# Ethernet.net
KiCad netlist of a schematic drawn in Altium Designer
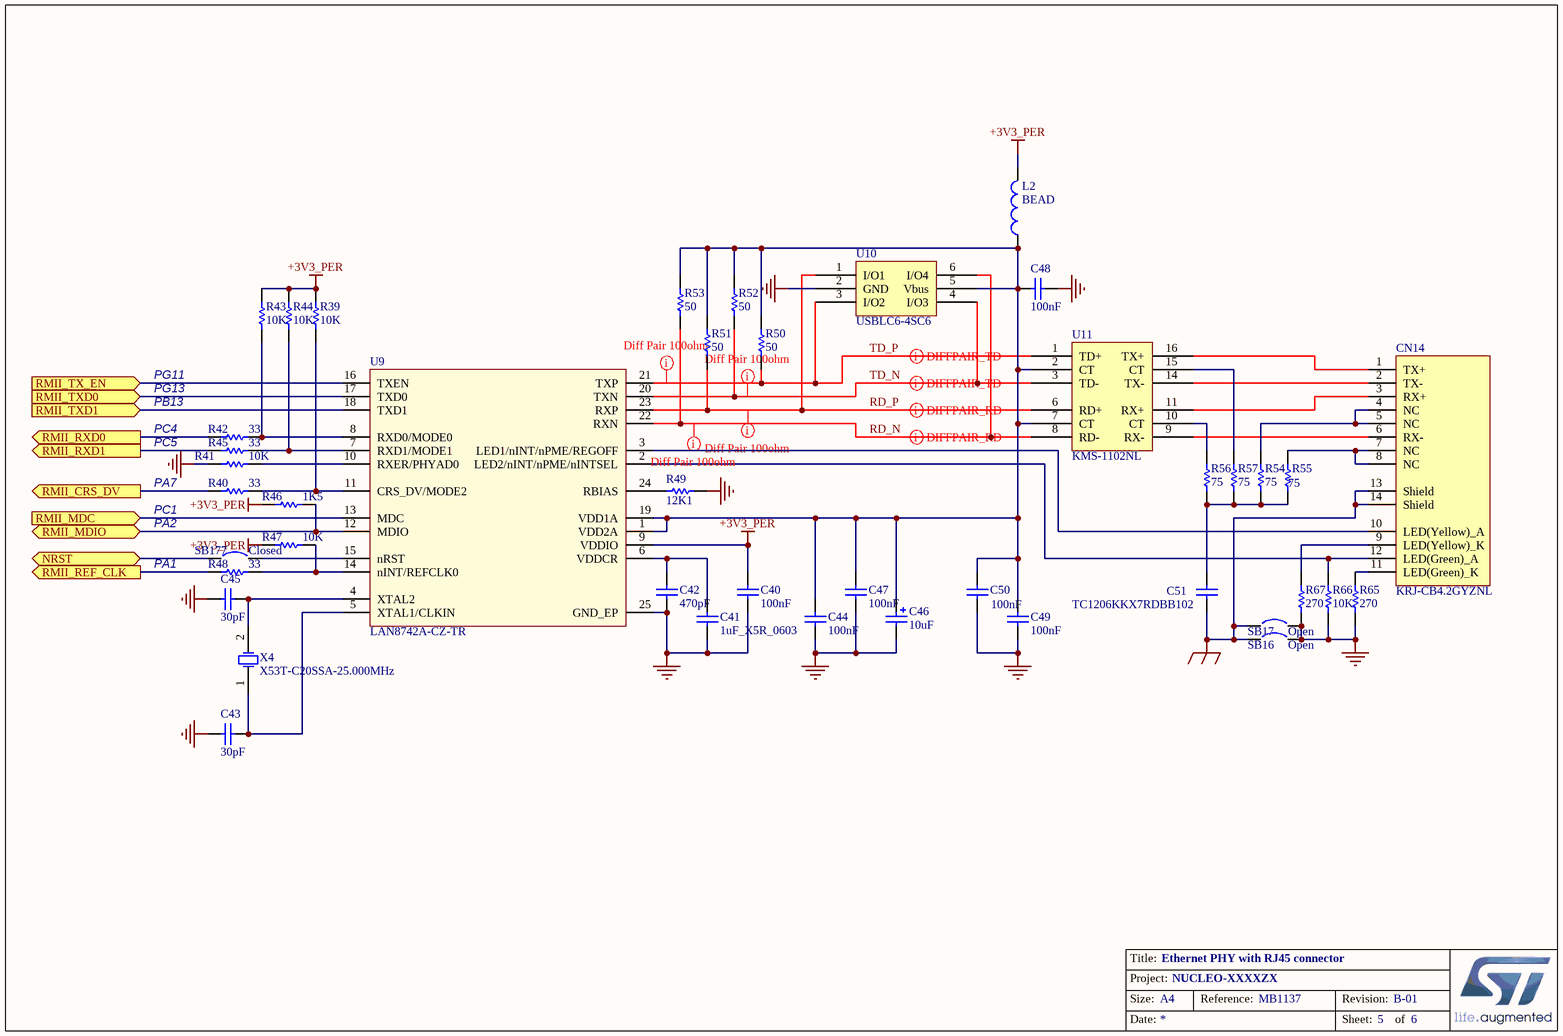
[diagram p0: Ethernet.SchDoc]

(export (version "E")
  (design (tool "Eeschema 10.0.6"))
  (components
    (comp (ref "C40")
      (value "100nF")
      (footprint "0603C")
      (description "Capacitor 0402 / 0603 / 0805")
      (libsource (lib "MCD_TOOLS") (part "Capacitor_ST"))
    )
    (comp (ref "C41")
      (value "1uF_X5R_0603")
      (footprint "0603C")
      (description "0603  X5R 1µF")
      (fields (field (name "TOLERANCE") "10%"))
      (libsource (lib "MB963_1") (part "CAP SMD 0603  X5R 1µF 25V 10%"))
    )
    (comp (ref "C42")
      (value "470pF")
      (footprint "0603C")
      (description "Capacitor 0402 / 0603 / 0805")
      (libsource (lib "MCD_TOOLS") (part "Capacitor_ST"))
    )
    (comp (ref "C43")
      (value "30pF")
      (footprint "0603C")
      (description "Capacitor 0402 / 0603 / 0805")
      (libsource (lib "MCD_TOOLS") (part "Capacitor_ST"))
    )
    (comp (ref "C44")
      (value "100nF")
      (footprint "0603C")
      (description "Capacitor 0402 / 0603 / 0805")
      (libsource (lib "MCD_TOOLS") (part "Capacitor_ST"))
    )
    (comp (ref "C45")
      (value "30pF")
      (footprint "0603C")
      (description "Capacitor 0402 / 0603 / 0805")
      (libsource (lib "MCD_TOOLS") (part "Capacitor_ST"))
    )
    (comp (ref "C46")
      (value "10uF")
      (footprint "TAN-A")
      (description "Polarized Capacitor,10uF,10V,10%,typeA,VISHAY")
      (libsource (lib "MCD_TOOLS") (part "Cap_10uF_POL_10%_TANA"))
    )
    (comp (ref "C47")
      (value "100nF")
      (footprint "0603C")
      (description "Capacitor 0402 / 0603 / 0805")
      (libsource (lib "MCD_TOOLS") (part "Capacitor_ST"))
    )
    (comp (ref "C48")
      (value "100nF")
      (footprint "0603C")
      (description "Capacitor 0402 / 0603 / 0805")
      (libsource (lib "MCD_TOOLS") (part "Capacitor_ST"))
    )
    (comp (ref "C49")
      (value "100nF")
      (footprint "0603C")
      (description "Capacitor 0402 / 0603 / 0805")
      (libsource (lib "MCD_TOOLS") (part "Capacitor_ST"))
    )
    (comp (ref "C50")
      (value "100nF")
      (footprint "0603C")
      (description "Capacitor 0402 / 0603 / 0805")
      (libsource (lib "MCD_TOOLS") (part "Capacitor_ST"))
    )
    (comp (ref "C51")
      (value "TC1206KKX7RDBB102")
      (footprint "1206C")
      (description "Capacitor 0402 / 0603 / 0805/ 1206")
      (libsource (lib "MCD_TOOLS") (part "Capacitor_ST"))
    )
    (comp (ref "CN14")
      (value "KRJ-CB4.2GYZNL")
      (footprint "RJ45_KRJ-CB4.2GYZNL")
      (description "100 Base-TX (Fast Ethernet) SMD RJ45 single port (1x1) with LEDS Integrated Magnetics Connector")
      (libsource (lib "MB1137") (part "KRJ-CB4.2GYZNL"))
    )
    (comp (ref "L2")
      (value "BEAD")
      (footprint "0603L")
      (description "Inductor")
      (fields (field (name "PUBLISHER") "Altium Limited"))
      (libsource (lib "Miscellaneous Devices") (part "Inductor"))
    )
    (comp (ref "R39")
      (value "10K")
      (footprint "0603R")
      (description "Resistor 0402 or 0603 or 0805")
      (libsource (lib "Miscellaneous Devices") (part "Res1"))
    )
    (comp (ref "R40")
      (value "33")
      (footprint "0603R")
      (description "Resistor,33,0402,1%,YAGEO")
      (libsource (lib "MCD_TOOLS") (part "Res_33_1%_0402"))
    )
    (comp (ref "R41")
      (value "10K")
      (footprint "0603R")
      (description "Resistor 0402 or 0603 or 0805")
      (libsource (lib "Miscellaneous Devices") (part "Res1"))
    )
    (comp (ref "R42")
      (value "33")
      (footprint "0603R")
      (description "Resistor,33,0402,1%,YAGEO")
      (libsource (lib "MCD_TOOLS") (part "Res_33_1%_0402"))
    )
    (comp (ref "R43")
      (value "10K")
      (footprint "0603R")
      (description "Resistor 0402 or 0603 or 0805")
      (libsource (lib "Miscellaneous Devices") (part "Res1"))
    )
    (comp (ref "R44")
      (value "10K")
      (footprint "0603R")
      (description "Resistor 0402 or 0603 or 0805")
      (libsource (lib "Miscellaneous Devices") (part "Res1"))
    )
    (comp (ref "R45")
      (value "33")
      (footprint "0603R")
      (description "Resistor,33,0402,1%,YAGEO")
      (libsource (lib "MCD_TOOLS") (part "Res_33_1%_0402"))
    )
    (comp (ref "R46")
      (value "1K5")
      (footprint "0603R")
      (description "Resistor,1K5,0402,1%,YAGEO")
      (libsource (lib "MCD_TOOLS") (part "Res_1K5_1%_0402"))
    )
    (comp (ref "R47")
      (value "10K")
      (footprint "0603R")
      (description "Resistor 0402 or 0603 or 0805")
      (libsource (lib "Miscellaneous Devices") (part "Res1"))
    )
    (comp (ref "R48")
      (value "33")
      (footprint "0603R")
      (description "Resistor,33,0402,1%,YAGEO")
      (libsource (lib "MCD_TOOLS") (part "Res_33_1%_0402"))
    )
    (comp (ref "R49")
      (value "12K1")
      (footprint "0603R")
      (description "Resistor,12K1,0603,1%,VISHAY")
      (libsource (lib "MCD_TOOLS") (part "Res_12K1_1%_0603"))
    )
    (comp (ref "R50")
      (value "50")
      (footprint "0603R")
      (description "Resistor,50,0402,1%,YAGEO")
      (libsource (lib "MB1137") (part "Res_50_1%_0603"))
    )
    (comp (ref "R51")
      (value "50")
      (footprint "0603R")
      (description "Resistor,50,0402,1%,YAGEO")
      (libsource (lib "MB1137") (part "Res_50_1%_0603"))
    )
    (comp (ref "R52")
      (value "50")
      (footprint "0603R")
      (description "Resistor,50,0402,1%,YAGEO")
      (libsource (lib "MB1137") (part "Res_50_1%_0603"))
    )
    (comp (ref "R53")
      (value "50")
      (footprint "0603R")
      (description "Resistor,50,0402,1%,YAGEO")
      (libsource (lib "MB1137") (part "Res_50_1%_0603"))
    )
    (comp (ref "R54")
      (value "75")
      (footprint "0603R")
      (description "Resistor,50,0402,1%,YAGEO")
      (libsource (lib "MB1137") (part "Res_75_1%_0603"))
    )
    (comp (ref "R55")
      (value "75")
      (footprint "0603R")
      (description "Resistor,50,0402,1%,YAGEO")
      (libsource (lib "MB1137") (part "Res_75_1%_0603"))
    )
    (comp (ref "R56")
      (value "75")
      (footprint "0603R")
      (description "Resistor,50,0402,1%,YAGEO")
      (libsource (lib "MB1137") (part "Res_75_1%_0603"))
    )
    (comp (ref "R57")
      (value "75")
      (footprint "0603R")
      (description "Resistor,50,0402,1%,YAGEO")
      (libsource (lib "MB1137") (part "Res_75_1%_0603"))
    )
    (comp (ref "R65")
      (value "270")
      (footprint "0603R")
      (description "Resistor 0402 or 0603 or 0805")
      (libsource (lib "Miscellaneous Devices") (part "Res1"))
    )
    (comp (ref "R66")
      (value "10K")
      (footprint "0603R")
      (description "Resistor 0402 or 0603 or 0805")
      (libsource (lib "Miscellaneous Devices") (part "Res1"))
    )
    (comp (ref "R67")
      (value "270")
      (footprint "0603R")
      (description "Resistor 0402 or 0603 or 0805")
      (libsource (lib "Miscellaneous Devices") (part "Res1"))
    )
    (comp (ref "SB16")
      (value "Open")
      (footprint "SB_0603")
      (description "Circuit Breaker")
      (fields (field (name "PUBLISHER") "Altium Limited"))
      (libsource (lib "MB1167") (part "Circuit Breaker"))
    )
    (comp (ref "SB17")
      (value "Open")
      (footprint "SB_0603")
      (description "Circuit Breaker")
      (fields (field (name "PUBLISHER") "Altium Limited"))
      (libsource (lib "MB1167") (part "Circuit Breaker"))
    )
    (comp (ref "SB177")
      (value "Closed")
      (footprint "SB_0603")
      (description "Circuit Breaker")
      (fields (field (name "PUBLISHER") "Altium Limited"))
      (libsource (lib "MB1167") (part "Circuit Breaker_close"))
    )
    (comp (ref "U9")
      (value "LAN8742A-CZ-TR")
      (footprint "QFN24_0R5_4X4")
      (libsource (lib "MB1137") (part "LAN8742A-CZ-TR"))
    )
    (comp (ref "U10")
      (value "USBLC6-4SC6")
      (footprint "SOT23-6L")
      (libsource (lib "MB1137_1") (part "USBLC6-4SC6"))
    )
    (comp (ref "U11")
      (value "KMS-1102NL")
      (footprint "Transformer")
      (libsource (lib "MB1137") (part "KMS-1102NL"))
    )
    (comp (ref "X4")
      (value "X53T-C20SSA-25.000MHz")
      (footprint "XTAL_2SM_5R0X3R2")
      (description "Crystal Oscillator")
      (fields (field (name "PUBLISHER") "Altium Limited"))
      (libsource (lib "MB1137") (part "XTAL_5032"))
    )
  )
  (nets
    (net (code "1") (name "+3V3_PER") (class "Default")
      (node (ref "C40") (pin "2") (pinfunction "2_2") (pintype "passive"))
      (node (ref "L2") (pin "2") (pinfunction "2_2") (pintype "passive"))
      (node (ref "R39") (pin "1") (pinfunction "1_1") (pintype "passive"))
      (node (ref "R43") (pin "1") (pinfunction "1_1") (pintype "passive"))
      (node (ref "R44") (pin "1") (pinfunction "1_1") (pintype "passive"))
      (node (ref "R46") (pin "2") (pinfunction "2_2") (pintype "passive"))
      (node (ref "R47") (pin "1") (pinfunction "1_1") (pintype "passive"))
      (node (ref "U9") (pin "9") (pinfunction "VDDIO_9") (pintype "passive"))
    )
    (net (code "2") (name "/NRST") (class "Default")
      (node (ref "SB177") (pin "1") (pinfunction "1_1") (pintype "passive"))
    )
    (net (code "3") (name "/RD_N") (class "Default")
      (node (ref "R53") (pin "1") (pinfunction "1_1") (pintype "passive"))
      (node (ref "U10") (pin "6") (pinfunction "I/O4_6") (pintype "passive"))
      (node (ref "U11") (pin "8") (pinfunction "RD-_8") (pintype "passive"))
      (node (ref "U9") (pin "22") (pinfunction "RXN_22") (pintype "passive"))
    )
    (net (code "4") (name "/RD_P") (class "Default")
      (node (ref "R51") (pin "1") (pinfunction "1_1") (pintype "passive"))
      (node (ref "U10") (pin "1") (pinfunction "I/O1_1") (pintype "passive"))
      (node (ref "U11") (pin "6") (pinfunction "RD+_6") (pintype "passive"))
      (node (ref "U9") (pin "23") (pinfunction "RXP_23") (pintype "passive"))
    )
    (net (code "5") (name "/RMII_CRS_DV") (class "Default")
      (node (ref "R40") (pin "2") (pinfunction "2_2") (pintype "passive"))
    )
    (net (code "6") (name "/RMII_MDC") (class "Default")
      (node (ref "U9") (pin "13") (pinfunction "MDC_13") (pintype "passive"))
    )
    (net (code "7") (name "/RMII_MDIO") (class "Default")
      (node (ref "R46") (pin "1") (pinfunction "1_1") (pintype "passive"))
      (node (ref "U9") (pin "12") (pinfunction "MDIO_12") (pintype "passive"))
    )
    (net (code "8") (name "/RMII_REF_CLK") (class "Default")
      (node (ref "R48") (pin "2") (pinfunction "2_2") (pintype "passive"))
    )
    (net (code "9") (name "/RMII_RXD0") (class "Default")
      (node (ref "R42") (pin "2") (pinfunction "2_2") (pintype "passive"))
    )
    (net (code "10") (name "/RMII_RXD1") (class "Default")
      (node (ref "R45") (pin "2") (pinfunction "2_2") (pintype "passive"))
    )
    (net (code "11") (name "/RMII_TXD0") (class "Default")
      (node (ref "U9") (pin "17") (pinfunction "TXD0_17") (pintype "passive"))
    )
    (net (code "12") (name "/RMII_TXD1") (class "Default")
      (node (ref "U9") (pin "18") (pinfunction "TXD1_18") (pintype "passive"))
    )
    (net (code "13") (name "/RMII_TX_EN") (class "Default")
      (node (ref "U9") (pin "16") (pinfunction "TXEN_16") (pintype "passive"))
    )
    (net (code "14") (name "/TD_N") (class "Default")
      (node (ref "R52") (pin "1") (pinfunction "1_1") (pintype "passive"))
      (node (ref "U10") (pin "4") (pinfunction "I/O3_4") (pintype "passive"))
      (node (ref "U11") (pin "3") (pinfunction "TD-_3") (pintype "passive"))
      (node (ref "U9") (pin "20") (pinfunction "TXN_20") (pintype "passive"))
    )
    (net (code "15") (name "/TD_P") (class "Default")
      (node (ref "R50") (pin "1") (pinfunction "1_1") (pintype "passive"))
      (node (ref "U10") (pin "3") (pinfunction "I/O2_3") (pintype "passive"))
      (node (ref "U11") (pin "1") (pinfunction "TD+_1") (pintype "passive"))
      (node (ref "U9") (pin "21") (pinfunction "TXP_21") (pintype "passive"))
    )
    (net (code "16") (name "EGND") (class "Default")
      (node (ref "C51") (pin "1") (pinfunction "1_1") (pintype "passive"))
      (node (ref "CN14") (pin "13") (pinfunction "Shield_13") (pintype "passive"))
      (node (ref "CN14") (pin "14") (pinfunction "Shield_14") (pintype "passive"))
      (node (ref "SB16") (pin "1") (pinfunction "1_1") (pintype "passive"))
      (node (ref "SB17") (pin "1") (pinfunction "1_1") (pintype "passive"))
    )
    (net (code "17") (name "GND") (class "Default")
      (node (ref "C40") (pin "1") (pinfunction "1_1") (pintype "passive"))
      (node (ref "C41") (pin "2") (pinfunction "2_2") (pintype "passive"))
      (node (ref "C42") (pin "1") (pinfunction "1_1") (pintype "passive"))
      (node (ref "C43") (pin "2") (pinfunction "2_2") (pintype "passive"))
      (node (ref "C44") (pin "1") (pinfunction "1_1") (pintype "passive"))
      (node (ref "C45") (pin "2") (pinfunction "2_2") (pintype "passive"))
      (node (ref "C46") (pin "2") (pinfunction "2_2") (pintype "passive"))
      (node (ref "C47") (pin "1") (pinfunction "1_1") (pintype "passive"))
      (node (ref "C48") (pin "1") (pinfunction "1_1") (pintype "passive"))
      (node (ref "C49") (pin "1") (pinfunction "1_1") (pintype "passive"))
      (node (ref "C50") (pin "1") (pinfunction "1_1") (pintype "passive"))
      (node (ref "R41") (pin "2") (pinfunction "2_2") (pintype "passive"))
      (node (ref "R49") (pin "2") (pinfunction "2_2") (pintype "passive"))
      (node (ref "R65") (pin "2") (pinfunction "2_2") (pintype "passive"))
      (node (ref "R66") (pin "2") (pinfunction "2_2") (pintype "passive"))
      (node (ref "R67") (pin "2") (pinfunction "2_2") (pintype "passive"))
      (node (ref "SB16") (pin "2") (pinfunction "2_2") (pintype "passive"))
      (node (ref "SB17") (pin "2") (pinfunction "2_2") (pintype "passive"))
      (node (ref "U10") (pin "2") (pinfunction "GND_2") (pintype "passive"))
      (node (ref "U9") (pin "25") (pinfunction "GND_EP_25") (pintype "passive"))
    )
    (net (code "18") (name "Net-(C51-Pad2)") (class "Default")
      (node (ref "C51") (pin "2") (pinfunction "2_2") (pintype "passive"))
      (node (ref "R54") (pin "1") (pinfunction "1_1") (pintype "passive"))
      (node (ref "R55") (pin "1") (pinfunction "1_1") (pintype "passive"))
      (node (ref "R56") (pin "1") (pinfunction "1_1") (pintype "passive"))
      (node (ref "R57") (pin "1") (pinfunction "1_1") (pintype "passive"))
    )
    (net (code "19") (name "Net-(CN14-LED(Green)_A)") (class "Default")
      (node (ref "CN14") (pin "12") (pinfunction "LED(Green)_A_12") (pintype "passive"))
      (node (ref "R66") (pin "1") (pinfunction "1_1") (pintype "passive"))
      (node (ref "U9") (pin "2") (pinfunction "LED2/nINT/nPME/nINTSEL_2") (pintype "passive"))
    )
    (net (code "20") (name "Net-(CN14-LED(Green)_K)") (class "Default")
      (node (ref "CN14") (pin "11") (pinfunction "LED(Green)_K_11") (pintype "passive"))
      (node (ref "R65") (pin "1") (pinfunction "1_1") (pintype "passive"))
    )
    (net (code "21") (name "Net-(CN14-LED(Yellow)_A)") (class "Default")
      (node (ref "CN14") (pin "10") (pinfunction "LED(Yellow)_A_10") (pintype "passive"))
      (node (ref "U9") (pin "3") (pinfunction "LED1/nINT/nPME/REGOFF_3") (pintype "passive"))
    )
    (net (code "22") (name "Net-(CN14-LED(Yellow)_K)") (class "Default")
      (node (ref "CN14") (pin "9") (pinfunction "LED(Yellow)_K_9") (pintype "passive"))
      (node (ref "R67") (pin "1") (pinfunction "1_1") (pintype "passive"))
    )
    (net (code "23") (name "Net-(CN14-NC-Pad4)") (class "Default")
      (node (ref "CN14") (pin "4") (pinfunction "NC_4") (pintype "passive"))
      (node (ref "CN14") (pin "5") (pinfunction "NC_5") (pintype "passive"))
      (node (ref "R54") (pin "2") (pinfunction "2_2") (pintype "passive"))
    )
    (net (code "24") (name "Net-(CN14-NC-Pad7)") (class "Default")
      (node (ref "CN14") (pin "7") (pinfunction "NC_7") (pintype "passive"))
      (node (ref "CN14") (pin "8") (pinfunction "NC_8") (pintype "passive"))
      (node (ref "R55") (pin "2") (pinfunction "2_2") (pintype "passive"))
    )
    (net (code "25") (name "Net-(CN14-RX+)") (class "Default")
      (node (ref "CN14") (pin "3") (pinfunction "RX+_3") (pintype "passive"))
      (node (ref "U11") (pin "11") (pinfunction "RX+_11") (pintype "passive"))
    )
    (net (code "26") (name "Net-(CN14-RX-)") (class "Default")
      (node (ref "CN14") (pin "6") (pinfunction "RX-_6") (pintype "passive"))
      (node (ref "U11") (pin "9") (pinfunction "RX-_9") (pintype "passive"))
    )
    (net (code "27") (name "Net-(CN14-TX+)") (class "Default")
      (node (ref "CN14") (pin "1") (pinfunction "TX+_1") (pintype "passive"))
      (node (ref "U11") (pin "16") (pinfunction "TX+_16") (pintype "passive"))
    )
    (net (code "28") (name "Net-(CN14-TX-)") (class "Default")
      (node (ref "CN14") (pin "2") (pinfunction "TX-_2") (pintype "passive"))
      (node (ref "U11") (pin "14") (pinfunction "TX-_14") (pintype "passive"))
    )
    (net (code "29") (name "Net-(R56-Pad2)") (class "Default")
      (node (ref "R56") (pin "2") (pinfunction "2_2") (pintype "passive"))
      (node (ref "U11") (pin "10") (pinfunction "CT_10") (pintype "passive"))
    )
    (net (code "30") (name "Net-(R57-Pad2)") (class "Default")
      (node (ref "R57") (pin "2") (pinfunction "2_2") (pintype "passive"))
      (node (ref "U11") (pin "15") (pinfunction "CT_15") (pintype "passive"))
    )
    (net (code "31") (name "Net-(U9-CRS_DV{slash}MODE2)") (class "Default")
      (node (ref "R39") (pin "2") (pinfunction "2_2") (pintype "passive"))
      (node (ref "R40") (pin "1") (pinfunction "1_1") (pintype "passive"))
      (node (ref "U9") (pin "11") (pinfunction "CRS_DV/MODE2_11") (pintype "passive"))
    )
    (net (code "32") (name "Net-(U9-RBIAS)") (class "Default")
      (node (ref "R49") (pin "1") (pinfunction "1_1") (pintype "passive"))
      (node (ref "U9") (pin "24") (pinfunction "RBIAS_24") (pintype "passive"))
    )
    (net (code "33") (name "Net-(U9-RXD0{slash}MODE0)") (class "Default")
      (node (ref "R42") (pin "1") (pinfunction "1_1") (pintype "passive"))
      (node (ref "R43") (pin "2") (pinfunction "2_2") (pintype "passive"))
      (node (ref "U9") (pin "8") (pinfunction "RXD0/MODE0_8") (pintype "passive"))
    )
    (net (code "34") (name "Net-(U9-RXD1{slash}MODE1)") (class "Default")
      (node (ref "R44") (pin "2") (pinfunction "2_2") (pintype "passive"))
      (node (ref "R45") (pin "1") (pinfunction "1_1") (pintype "passive"))
      (node (ref "U9") (pin "7") (pinfunction "RXD1/MODE1_7") (pintype "passive"))
    )
    (net (code "35") (name "Net-(U9-RXER{slash}PHYAD0)") (class "Default")
      (node (ref "R41") (pin "1") (pinfunction "1_1") (pintype "passive"))
      (node (ref "U9") (pin "10") (pinfunction "RXER/PHYAD0_10") (pintype "passive"))
    )
    (net (code "36") (name "Net-(U9-VDDCR)") (class "Default")
      (node (ref "C41") (pin "1") (pinfunction "1_1") (pintype "passive"))
      (node (ref "C42") (pin "2") (pinfunction "2_2") (pintype "passive"))
      (node (ref "U9") (pin "6") (pinfunction "VDDCR_6") (pintype "passive"))
    )
    (net (code "37") (name "Net-(U9-XTAL1{slash}CLKIN)") (class "Default")
      (node (ref "C43") (pin "1") (pinfunction "1_1") (pintype "passive"))
      (node (ref "U9") (pin "5") (pinfunction "XTAL1/CLKIN_5") (pintype "passive"))
      (node (ref "X4") (pin "1") (pinfunction "OSC1_1") (pintype "passive"))
    )
    (net (code "38") (name "Net-(U9-XTAL2)") (class "Default")
      (node (ref "C45") (pin "1") (pinfunction "1_1") (pintype "passive"))
      (node (ref "U9") (pin "4") (pinfunction "XTAL2_4") (pintype "passive"))
      (node (ref "X4") (pin "2") (pinfunction "OSC2_2") (pintype "passive"))
    )
    (net (code "39") (name "Net-(U9-nINT{slash}REFCLK0)") (class "Default")
      (node (ref "R47") (pin "2") (pinfunction "2_2") (pintype "passive"))
      (node (ref "R48") (pin "1") (pinfunction "1_1") (pintype "passive"))
      (node (ref "U9") (pin "14") (pinfunction "nINT/REFCLK0_14") (pintype "passive"))
    )
    (net (code "40") (name "Net-(U9-nRST)") (class "Default")
      (node (ref "SB177") (pin "2") (pinfunction "2_2") (pintype "passive"))
      (node (ref "U9") (pin "15") (pinfunction "nRST_15") (pintype "passive"))
    )
    (net (code "41") (name "Net-(U10-Vbus)") (class "Default")
      (node (ref "C44") (pin "2") (pinfunction "2_2") (pintype "passive"))
      (node (ref "C46") (pin "1") (pinfunction "1_1") (pintype "passive"))
      (node (ref "C47") (pin "2") (pinfunction "2_2") (pintype "passive"))
      (node (ref "C48") (pin "2") (pinfunction "2_2") (pintype "passive"))
      (node (ref "C49") (pin "2") (pinfunction "2_2") (pintype "passive"))
      (node (ref "C50") (pin "2") (pinfunction "2_2") (pintype "passive"))
      (node (ref "L2") (pin "1") (pinfunction "1_1") (pintype "passive"))
      (node (ref "R50") (pin "2") (pinfunction "2_2") (pintype "passive"))
      (node (ref "R51") (pin "2") (pinfunction "2_2") (pintype "passive"))
      (node (ref "R52") (pin "2") (pinfunction "2_2") (pintype "passive"))
      (node (ref "R53") (pin "2") (pinfunction "2_2") (pintype "passive"))
      (node (ref "U10") (pin "5") (pinfunction "Vbus_5") (pintype "passive"))
      (node (ref "U11") (pin "2") (pinfunction "CT_2") (pintype "passive"))
      (node (ref "U11") (pin "7") (pinfunction "CT_7") (pintype "passive"))
      (node (ref "U9") (pin "1") (pinfunction "VDD2A_1") (pintype "passive"))
      (node (ref "U9") (pin "19") (pinfunction "VDD1A_19") (pintype "passive"))
    )
  )
)
